# rapport.net
KiCad netlist of a schematic drawn in EAGLE
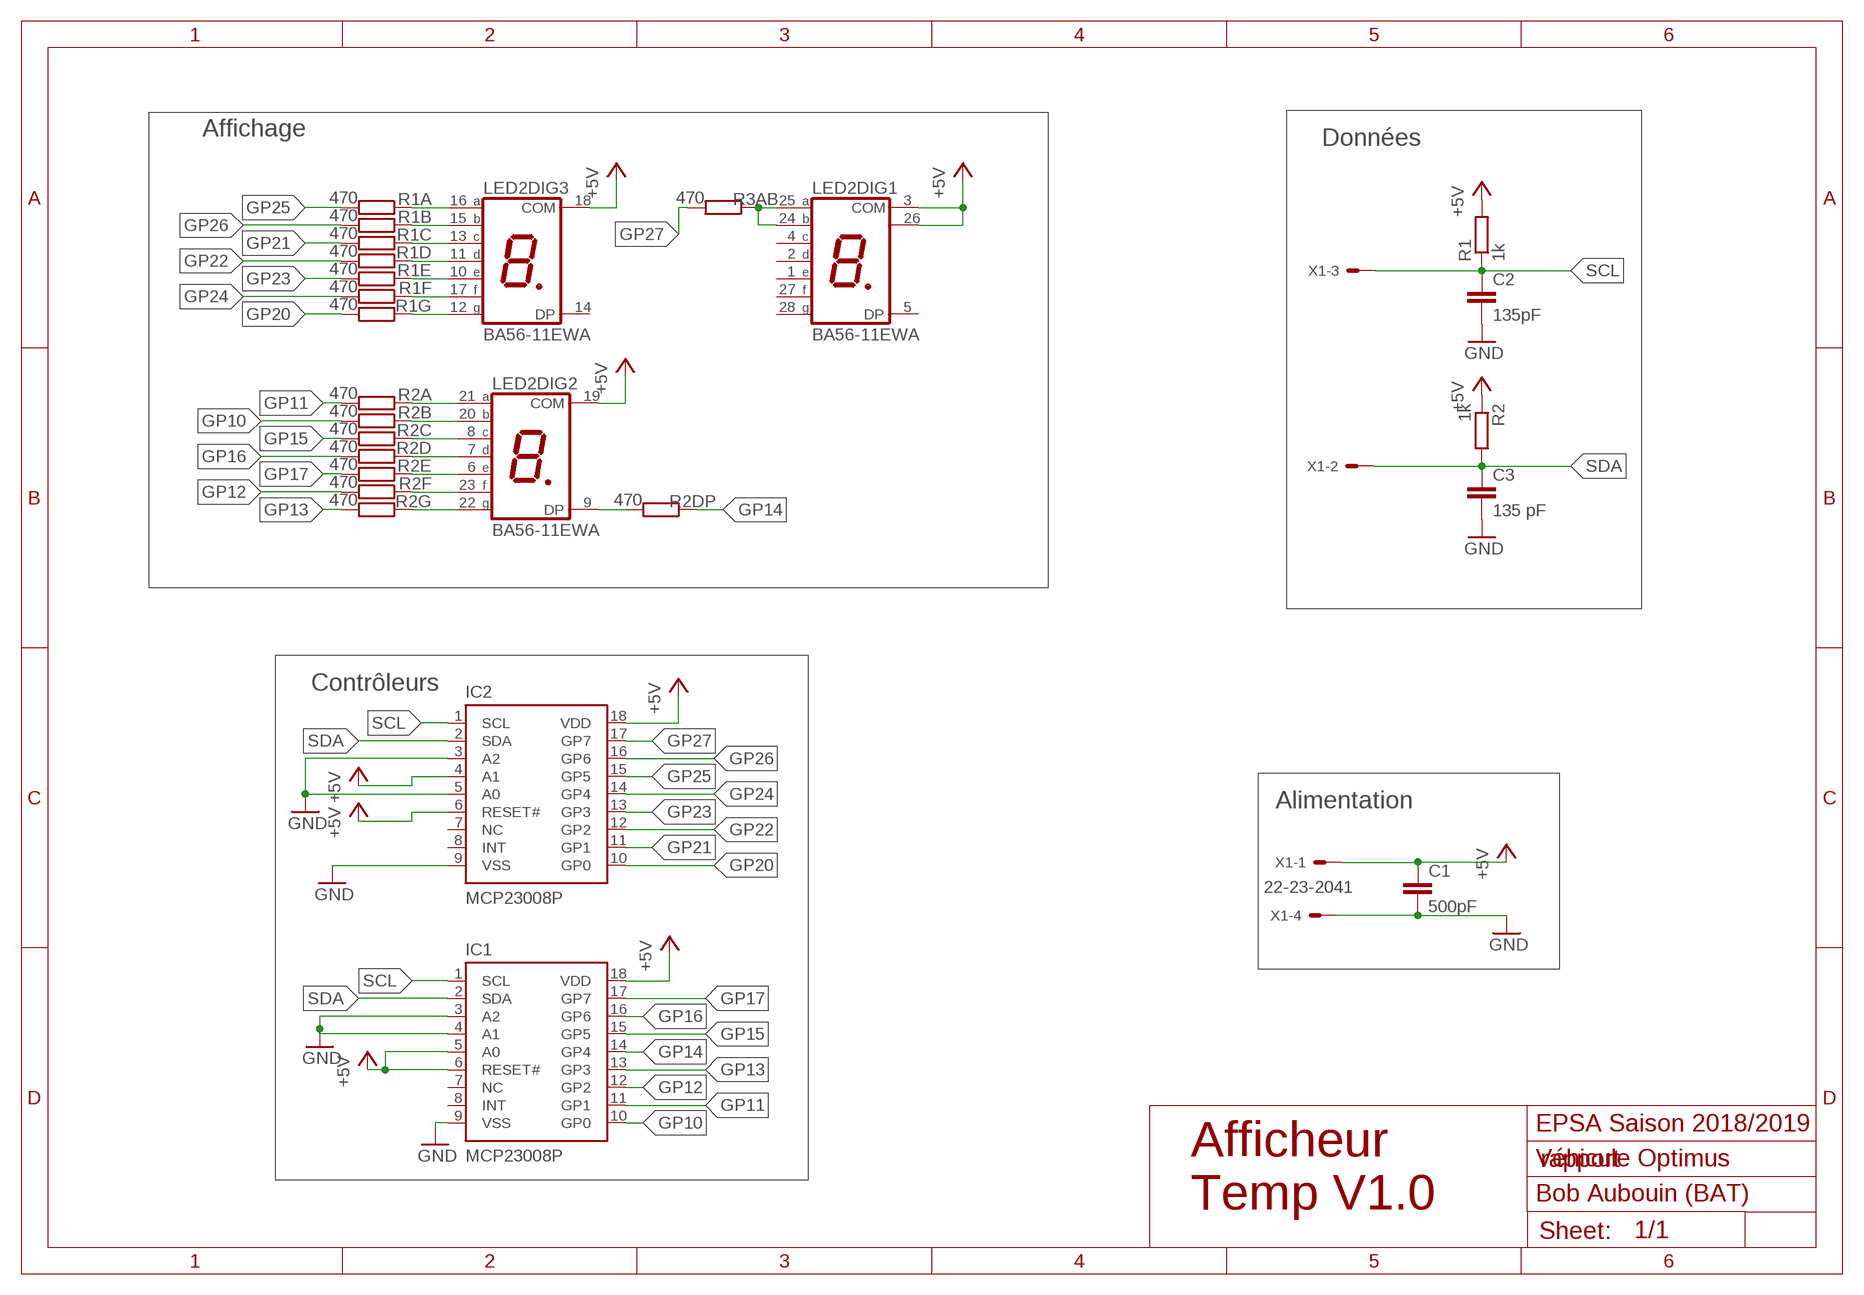
[diagram p0: schematic, sheet 1]

(export (version "E")
  (design (tool "Eeschema 10.0.6"))
  (components
    (comp (ref "C1")
      (value "500pF")
      (footprint "eagle-import:C025-025X050")
      (libsource (lib "eagle-import") (part "C-EU025-025X050"))
    )
    (comp (ref "C2")
      (value "135pF")
      (footprint "eagle-import:C025-025X050")
      (libsource (lib "eagle-import") (part "C-EU025-025X050"))
    )
    (comp (ref "C3")
      (value "135 pF")
      (footprint "eagle-import:C025-025X050")
      (libsource (lib "eagle-import") (part "C-EU025-025X050"))
    )
    (comp (ref "IC1")
      (value "MCP23008P")
      (footprint "eagle-import:DIL18")
      (libsource (lib "eagle-import") (part "MCP23008P"))
    )
    (comp (ref "IC2")
      (value "MCP23008P")
      (footprint "eagle-import:DIL18")
      (libsource (lib "eagle-import") (part "MCP23008P"))
    )
    (comp (ref "LED2")
      (value "BA56-11EWA")
      (footprint "eagle-import:BA_BC56")
      (libsource (lib "eagle-import") (part "B?56-11WAAE"))
    )
    (comp (ref "R1")
      (value "1k")
      (footprint "eagle-import:0204_7")
      (libsource (lib "eagle-import") (part "R-EU_0204/7"))
    )
    (comp (ref "R1A")
      (value "470")
      (footprint "eagle-import:0204_7")
      (libsource (lib "eagle-import") (part "R-EU_0204/7"))
    )
    (comp (ref "R1B")
      (value "470")
      (footprint "eagle-import:0204_7")
      (libsource (lib "eagle-import") (part "R-EU_0204/7"))
    )
    (comp (ref "R1C")
      (value "470")
      (footprint "eagle-import:0204_7")
      (libsource (lib "eagle-import") (part "R-EU_0204/7"))
    )
    (comp (ref "R1D")
      (value "470")
      (footprint "eagle-import:0204_7")
      (libsource (lib "eagle-import") (part "R-EU_0204/7"))
    )
    (comp (ref "R1E")
      (value "470")
      (footprint "eagle-import:0204_7")
      (libsource (lib "eagle-import") (part "R-EU_0204/7"))
    )
    (comp (ref "R1F")
      (value "470")
      (footprint "eagle-import:0204_7")
      (libsource (lib "eagle-import") (part "R-EU_0204/7"))
    )
    (comp (ref "R1G")
      (value "470")
      (footprint "eagle-import:0204_7")
      (libsource (lib "eagle-import") (part "R-EU_0204/7"))
    )
    (comp (ref "R2")
      (value "1k")
      (footprint "eagle-import:0204_7")
      (libsource (lib "eagle-import") (part "R-EU_0204/7"))
    )
    (comp (ref "R2A")
      (value "470")
      (footprint "eagle-import:0204_7")
      (libsource (lib "eagle-import") (part "R-EU_0204/7"))
    )
    (comp (ref "R2B")
      (value "470")
      (footprint "eagle-import:0204_7")
      (libsource (lib "eagle-import") (part "R-EU_0204/7"))
    )
    (comp (ref "R2C")
      (value "470")
      (footprint "eagle-import:0204_7")
      (libsource (lib "eagle-import") (part "R-EU_0204/7"))
    )
    (comp (ref "R2D")
      (value "470")
      (footprint "eagle-import:0204_7")
      (libsource (lib "eagle-import") (part "R-EU_0204/7"))
    )
    (comp (ref "R2DP")
      (value "470")
      (footprint "eagle-import:0204_7")
      (libsource (lib "eagle-import") (part "R-EU_0204/7"))
    )
    (comp (ref "R2E")
      (value "470")
      (footprint "eagle-import:0204_7")
      (libsource (lib "eagle-import") (part "R-EU_0204/7"))
    )
    (comp (ref "R2F")
      (value "470")
      (footprint "eagle-import:0204_7")
      (libsource (lib "eagle-import") (part "R-EU_0204/7"))
    )
    (comp (ref "R2G")
      (value "470")
      (footprint "eagle-import:0204_7")
      (libsource (lib "eagle-import") (part "R-EU_0204/7"))
    )
    (comp (ref "R3AB")
      (value "470")
      (footprint "eagle-import:0204_7")
      (libsource (lib "eagle-import") (part "R-EU_0204/7"))
    )
    (comp (ref "X1")
      (value "22-23-2041")
      (footprint "eagle-import:22-23-2041")
      (fields (field (name "MF") "MOLEX"))
      (libsource (lib "eagle-import") (part "22-23-2041"))
    )
  )
  (nets
    (net (code "1") (name "+5V") (class "Default")
      (node (ref "C1") (pin "1") (pinfunction "1_1") (pintype "passive"))
      (node (ref "IC1") (pin "18") (pinfunction "VDD_18") (pintype "power_in"))
      (node (ref "IC1") (pin "5") (pinfunction "A0_5") (pintype "input"))
      (node (ref "IC1") (pin "6") (pinfunction "RESET#_6") (pintype "input"))
      (node (ref "IC2") (pin "18") (pinfunction "VDD_18") (pintype "power_in"))
      (node (ref "IC2") (pin "4") (pinfunction "A1_4") (pintype "input"))
      (node (ref "IC2") (pin "6") (pinfunction "RESET#_6") (pintype "input"))
      (node (ref "LED2") (pin "18") (pinfunction "COM_18") (pintype "passive"))
      (node (ref "LED2") (pin "19") (pinfunction "COM_19") (pintype "passive"))
      (node (ref "LED2") (pin "26") (pinfunction "COM_26") (pintype "passive"))
      (node (ref "LED2") (pin "3") (pinfunction "COM_3") (pintype "passive"))
      (node (ref "R1") (pin "2") (pinfunction "2_2") (pintype "passive"))
      (node (ref "R2") (pin "1") (pinfunction "1_1") (pintype "passive"))
      (node (ref "X1") (pin "1") (pinfunction "S_1") (pintype "passive"))
    )
    (net (code "2") (name "GND") (class "Default")
      (node (ref "C1") (pin "2") (pinfunction "2_2") (pintype "passive"))
      (node (ref "C2") (pin "2") (pinfunction "2_2") (pintype "passive"))
      (node (ref "C3") (pin "2") (pinfunction "2_2") (pintype "passive"))
      (node (ref "IC1") (pin "3") (pinfunction "A2_3") (pintype "input"))
      (node (ref "IC1") (pin "4") (pinfunction "A1_4") (pintype "input"))
      (node (ref "IC1") (pin "9") (pinfunction "VSS_9") (pintype "power_in"))
      (node (ref "IC2") (pin "3") (pinfunction "A2_3") (pintype "input"))
      (node (ref "IC2") (pin "5") (pinfunction "A0_5") (pintype "input"))
      (node (ref "IC2") (pin "9") (pinfunction "VSS_9") (pintype "power_in"))
      (node (ref "X1") (pin "4") (pinfunction "S_4") (pintype "passive"))
    )
    (net (code "3") (name "GP10") (class "Default")
      (node (ref "IC1") (pin "10") (pinfunction "GP0_10") (pintype "bidirectional"))
      (node (ref "R2B") (pin "2") (pinfunction "2_2") (pintype "passive"))
    )
    (net (code "4") (name "GP11") (class "Default")
      (node (ref "IC1") (pin "11") (pinfunction "GP1_11") (pintype "bidirectional"))
      (node (ref "R2A") (pin "2") (pinfunction "2_2") (pintype "passive"))
    )
    (net (code "5") (name "GP12") (class "Default")
      (node (ref "IC1") (pin "12") (pinfunction "GP2_12") (pintype "bidirectional"))
      (node (ref "R2F") (pin "2") (pinfunction "2_2") (pintype "passive"))
    )
    (net (code "6") (name "GP13") (class "Default")
      (node (ref "IC1") (pin "13") (pinfunction "GP3_13") (pintype "bidirectional"))
      (node (ref "R2G") (pin "2") (pinfunction "2_2") (pintype "passive"))
    )
    (net (code "7") (name "GP14") (class "Default")
      (node (ref "IC1") (pin "14") (pinfunction "GP4_14") (pintype "bidirectional"))
      (node (ref "R2DP") (pin "1") (pinfunction "1_1") (pintype "passive"))
    )
    (net (code "8") (name "GP15") (class "Default")
      (node (ref "IC1") (pin "15") (pinfunction "GP5_15") (pintype "bidirectional"))
      (node (ref "R2C") (pin "2") (pinfunction "2_2") (pintype "passive"))
    )
    (net (code "9") (name "GP16") (class "Default")
      (node (ref "IC1") (pin "16") (pinfunction "GP6_16") (pintype "bidirectional"))
      (node (ref "R2D") (pin "2") (pinfunction "2_2") (pintype "passive"))
    )
    (net (code "10") (name "GP17") (class "Default")
      (node (ref "IC1") (pin "17") (pinfunction "GP7_17") (pintype "bidirectional"))
      (node (ref "R2E") (pin "2") (pinfunction "2_2") (pintype "passive"))
    )
    (net (code "11") (name "GP20") (class "Default")
      (node (ref "IC2") (pin "10") (pinfunction "GP0_10") (pintype "bidirectional"))
      (node (ref "R1G") (pin "2") (pinfunction "2_2") (pintype "passive"))
    )
    (net (code "12") (name "GP21") (class "Default")
      (node (ref "IC2") (pin "11") (pinfunction "GP1_11") (pintype "bidirectional"))
      (node (ref "R1C") (pin "2") (pinfunction "2_2") (pintype "passive"))
    )
    (net (code "13") (name "GP22") (class "Default")
      (node (ref "IC2") (pin "12") (pinfunction "GP2_12") (pintype "bidirectional"))
      (node (ref "R1D") (pin "2") (pinfunction "2_2") (pintype "passive"))
    )
    (net (code "14") (name "GP23") (class "Default")
      (node (ref "IC2") (pin "13") (pinfunction "GP3_13") (pintype "bidirectional"))
      (node (ref "R1E") (pin "2") (pinfunction "2_2") (pintype "passive"))
    )
    (net (code "15") (name "GP24") (class "Default")
      (node (ref "IC2") (pin "14") (pinfunction "GP4_14") (pintype "bidirectional"))
      (node (ref "R1F") (pin "2") (pinfunction "2_2") (pintype "passive"))
    )
    (net (code "16") (name "GP25") (class "Default")
      (node (ref "IC2") (pin "15") (pinfunction "GP5_15") (pintype "bidirectional"))
      (node (ref "R1A") (pin "2") (pinfunction "2_2") (pintype "passive"))
    )
    (net (code "17") (name "GP26") (class "Default")
      (node (ref "IC2") (pin "16") (pinfunction "GP6_16") (pintype "bidirectional"))
      (node (ref "R1B") (pin "2") (pinfunction "2_2") (pintype "passive"))
    )
    (net (code "18") (name "GP27") (class "Default")
      (node (ref "IC2") (pin "17") (pinfunction "GP7_17") (pintype "bidirectional"))
      (node (ref "R3AB") (pin "2") (pinfunction "2_2") (pintype "passive"))
    )
    (net (code "19") (name "Net-(LED2A-A)") (class "Default")
      (node (ref "LED2") (pin "24") (pinfunction "B_24") (pintype "passive"))
      (node (ref "LED2") (pin "25") (pinfunction "A_25") (pintype "passive"))
      (node (ref "R3AB") (pin "1") (pinfunction "1_1") (pintype "passive"))
    )
    (net (code "20") (name "Net-(LED2B-A)") (class "Default")
      (node (ref "LED2") (pin "21") (pinfunction "A_21") (pintype "passive"))
      (node (ref "R2A") (pin "1") (pinfunction "1_1") (pintype "passive"))
    )
    (net (code "21") (name "Net-(LED2B-B)") (class "Default")
      (node (ref "LED2") (pin "20") (pinfunction "B_20") (pintype "passive"))
      (node (ref "R2B") (pin "1") (pinfunction "1_1") (pintype "passive"))
    )
    (net (code "22") (name "Net-(LED2B-C)") (class "Default")
      (node (ref "LED2") (pin "8") (pinfunction "C_8") (pintype "passive"))
      (node (ref "R2C") (pin "1") (pinfunction "1_1") (pintype "passive"))
    )
    (net (code "23") (name "Net-(LED2B-D)") (class "Default")
      (node (ref "LED2") (pin "7") (pinfunction "D_7") (pintype "passive"))
      (node (ref "R2D") (pin "1") (pinfunction "1_1") (pintype "passive"))
    )
    (net (code "24") (name "Net-(LED2B-DP)") (class "Default")
      (node (ref "LED2") (pin "9") (pinfunction "DP_9") (pintype "passive"))
      (node (ref "R2DP") (pin "2") (pinfunction "2_2") (pintype "passive"))
    )
    (net (code "25") (name "Net-(LED2B-E)") (class "Default")
      (node (ref "LED2") (pin "6") (pinfunction "E_6") (pintype "passive"))
      (node (ref "R2E") (pin "1") (pinfunction "1_1") (pintype "passive"))
    )
    (net (code "26") (name "Net-(LED2B-F)") (class "Default")
      (node (ref "LED2") (pin "23") (pinfunction "F_23") (pintype "passive"))
      (node (ref "R2F") (pin "1") (pinfunction "1_1") (pintype "passive"))
    )
    (net (code "27") (name "Net-(LED2B-G)") (class "Default")
      (node (ref "LED2") (pin "22") (pinfunction "G_22") (pintype "passive"))
      (node (ref "R2G") (pin "1") (pinfunction "1_1") (pintype "passive"))
    )
    (net (code "28") (name "Net-(LED2C-A)") (class "Default")
      (node (ref "LED2") (pin "16") (pinfunction "A_16") (pintype "passive"))
      (node (ref "R1A") (pin "1") (pinfunction "1_1") (pintype "passive"))
    )
    (net (code "29") (name "Net-(LED2C-B)") (class "Default")
      (node (ref "LED2") (pin "15") (pinfunction "B_15") (pintype "passive"))
      (node (ref "R1B") (pin "1") (pinfunction "1_1") (pintype "passive"))
    )
    (net (code "30") (name "Net-(LED2C-C)") (class "Default")
      (node (ref "LED2") (pin "13") (pinfunction "C_13") (pintype "passive"))
      (node (ref "R1C") (pin "1") (pinfunction "1_1") (pintype "passive"))
    )
    (net (code "31") (name "Net-(LED2C-D)") (class "Default")
      (node (ref "LED2") (pin "11") (pinfunction "D_11") (pintype "passive"))
      (node (ref "R1D") (pin "1") (pinfunction "1_1") (pintype "passive"))
    )
    (net (code "32") (name "Net-(LED2C-E)") (class "Default")
      (node (ref "LED2") (pin "10") (pinfunction "E_10") (pintype "passive"))
      (node (ref "R1E") (pin "1") (pinfunction "1_1") (pintype "passive"))
    )
    (net (code "33") (name "Net-(LED2C-F)") (class "Default")
      (node (ref "LED2") (pin "17") (pinfunction "F_17") (pintype "passive"))
      (node (ref "R1F") (pin "1") (pinfunction "1_1") (pintype "passive"))
    )
    (net (code "34") (name "Net-(LED2C-G)") (class "Default")
      (node (ref "LED2") (pin "12") (pinfunction "G_12") (pintype "passive"))
      (node (ref "R1G") (pin "1") (pinfunction "1_1") (pintype "passive"))
    )
    (net (code "35") (name "SCL") (class "Default")
      (node (ref "C2") (pin "1") (pinfunction "1_1") (pintype "passive"))
      (node (ref "IC1") (pin "1") (pinfunction "SCL_1") (pintype "input"))
      (node (ref "IC2") (pin "1") (pinfunction "SCL_1") (pintype "input"))
      (node (ref "R1") (pin "1") (pinfunction "1_1") (pintype "passive"))
      (node (ref "X1") (pin "3") (pinfunction "S_3") (pintype "passive"))
    )
    (net (code "36") (name "SDA") (class "Default")
      (node (ref "C3") (pin "1") (pinfunction "1_1") (pintype "passive"))
      (node (ref "IC1") (pin "2") (pinfunction "SDA_2") (pintype "bidirectional"))
      (node (ref "IC2") (pin "2") (pinfunction "SDA_2") (pintype "bidirectional"))
      (node (ref "R2") (pin "2") (pinfunction "2_2") (pintype "passive"))
      (node (ref "X1") (pin "2") (pinfunction "S_2") (pintype "passive"))
    )
    (net (code "37") (name "unconnected-(IC1-INT-Pad8)") (class "Default")
      (node (ref "IC1") (pin "8") (pinfunction "INT_8") (pintype "output"))
    )
    (net (code "38") (name "unconnected-(IC1-NC-Pad7)") (class "Default")
      (node (ref "IC1") (pin "7") (pinfunction "NC_7") (pintype "no_connect"))
    )
    (net (code "39") (name "unconnected-(IC2-INT-Pad8)") (class "Default")
      (node (ref "IC2") (pin "8") (pinfunction "INT_8") (pintype "output"))
    )
    (net (code "40") (name "unconnected-(IC2-NC-Pad7)") (class "Default")
      (node (ref "IC2") (pin "7") (pinfunction "NC_7") (pintype "no_connect"))
    )
    (net (code "41") (name "unconnected-(LED2A-C-Pad4)") (class "Default")
      (node (ref "LED2") (pin "4") (pinfunction "C_4") (pintype "passive"))
    )
    (net (code "42") (name "unconnected-(LED2A-D-Pad2)") (class "Default")
      (node (ref "LED2") (pin "2") (pinfunction "D_2") (pintype "passive"))
    )
    (net (code "43") (name "unconnected-(LED2A-DP-Pad5)") (class "Default")
      (node (ref "LED2") (pin "5") (pinfunction "DP_5") (pintype "passive"))
    )
    (net (code "44") (name "unconnected-(LED2A-E-Pad1)") (class "Default")
      (node (ref "LED2") (pin "1") (pinfunction "E_1") (pintype "passive"))
    )
    (net (code "45") (name "unconnected-(LED2A-F-Pad27)") (class "Default")
      (node (ref "LED2") (pin "27") (pinfunction "F_27") (pintype "passive"))
    )
    (net (code "46") (name "unconnected-(LED2A-G-Pad28)") (class "Default")
      (node (ref "LED2") (pin "28") (pinfunction "G_28") (pintype "passive"))
    )
    (net (code "47") (name "unconnected-(LED2C-DP-Pad14)") (class "Default")
      (node (ref "LED2") (pin "14") (pinfunction "DP_14") (pintype "passive"))
    )
  )
)
